# open-lab-mon-A.net
KiCad netlist of a schematic drawn in EAGLE
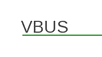
[diagram p0: schematic, sheet 1, part 1 of 2]
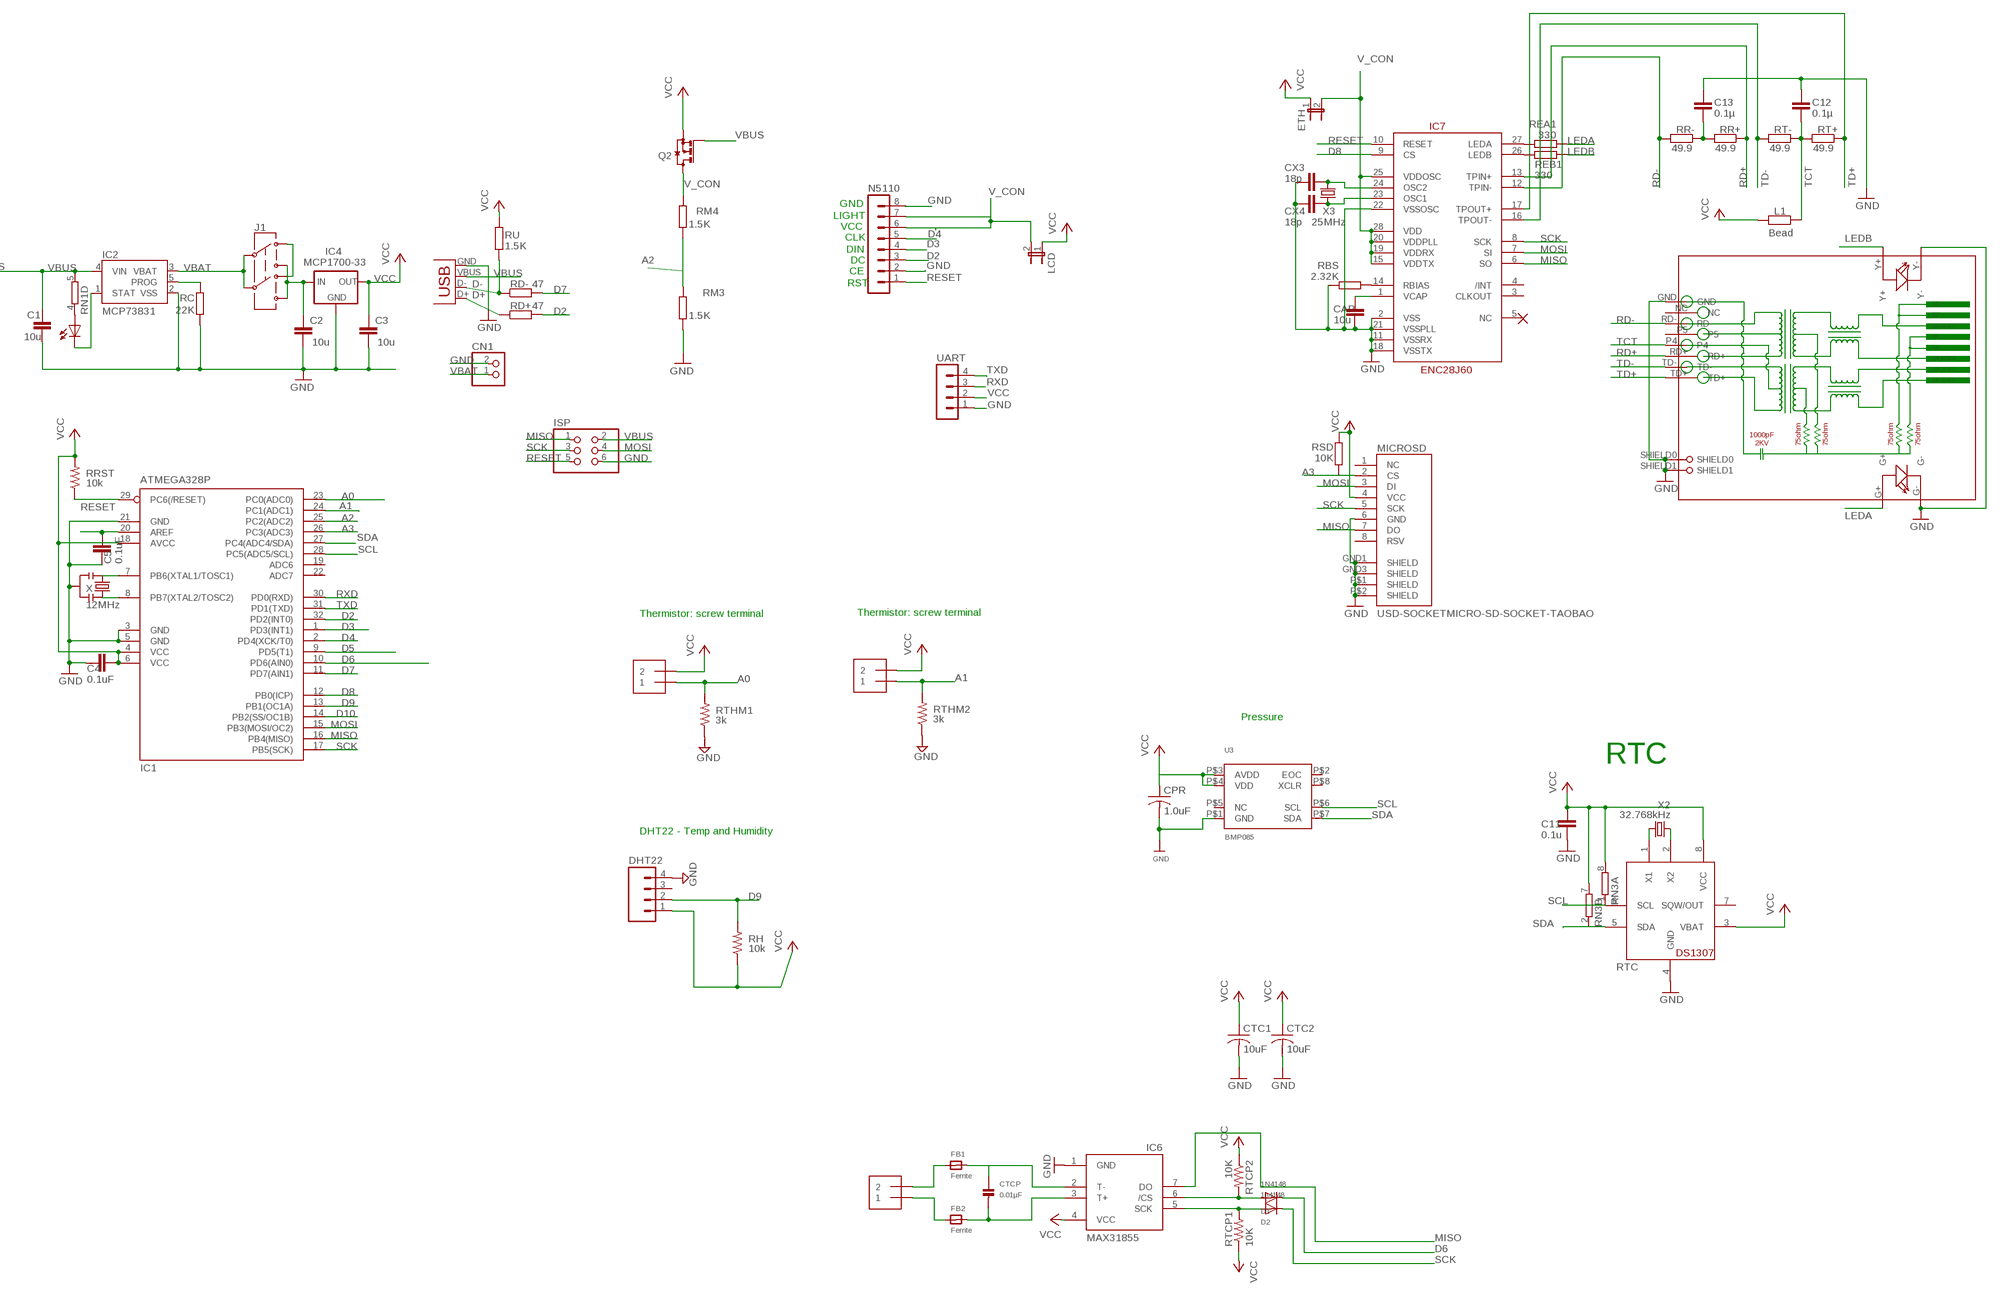
[diagram p1: schematic, sheet 1, part 2 of 2]

(export (version "E")
  (design (tool "Eeschema 10.0.6"))
  (components
    (comp (ref "C1")
      (value "10u")
      (footprint "eagle-import:C0805")
      (libsource (lib "eagle-import") (part "resistor_C-EUC0805"))
    )
    (comp (ref "C2")
      (value "10u")
      (footprint "eagle-import:C0805")
      (libsource (lib "eagle-import") (part "resistor_C-EUC0805"))
    )
    (comp (ref "C3")
      (value "10u")
      (footprint "eagle-import:C0805")
      (libsource (lib "eagle-import") (part "resistor_C-EUC0805"))
    )
    (comp (ref "C4")
      (value "0.1uF")
      (footprint "eagle-import:C0805")
      (libsource (lib "eagle-import") (part "C-EUC0805"))
    )
    (comp (ref "C5")
      (value "0.1uF")
      (footprint "eagle-import:C0805")
      (libsource (lib "eagle-import") (part "C-EUC0805"))
    )
    (comp (ref "C11")
      (value "0.1u")
      (footprint "eagle-import:C0805")
      (libsource (lib "eagle-import") (part "C-EUC0805"))
    )
    (comp (ref "C12")
      (value "0.1µ")
      (footprint "eagle-import:C0805")
      (libsource (lib "eagle-import") (part "resistor_C-EUC0805"))
    )
    (comp (ref "C13")
      (value "0.1µ")
      (footprint "eagle-import:C0805")
      (libsource (lib "eagle-import") (part "resistor_C-EUC0805"))
    )
    (comp (ref "CAP")
      (value "10u")
      (footprint "eagle-import:C0805")
      (libsource (lib "eagle-import") (part "resistor_C-EUC0805"))
    )
    (comp (ref "CHG")
      (value "0805")
      (footprint "eagle-import:CHIPLED_0805")
      (libsource (lib "eagle-import") (part "LEDCHIPLED_0805"))
    )
    (comp (ref "CN1")
      (value "JST_2PIN-SMT-RA")
      (footprint "eagle-import:JST-PH-2-SMT-RA")
      (libsource (lib "eagle-import") (part "JST_2PIN-SMT-RA"))
    )
    (comp (ref "CPR")
      (value "1.0uF")
      (footprint "eagle-import:C0805")
      (libsource (lib "eagle-import") (part "C-USC0805"))
    )
    (comp (ref "CTC1")
      (value "10uF")
      (footprint "eagle-import:C0805K")
      (libsource (lib "eagle-import") (part "C-USC0805K"))
    )
    (comp (ref "CTC2")
      (value "10uF")
      (footprint "eagle-import:C0805K")
      (libsource (lib "eagle-import") (part "C-USC0805K"))
    )
    (comp (ref "CTCP")
      (value "0.01µF")
      (footprint "eagle-import:_0805")
      (libsource (lib "eagle-import") (part "CAP_CERAMIC_0805"))
    )
    (comp (ref "CX3")
      (value "18p")
      (footprint "eagle-import:C0805")
      (libsource (lib "eagle-import") (part "resistor_C-EUC0805"))
    )
    (comp (ref "CX4")
      (value "18p")
      (footprint "eagle-import:C0805")
      (libsource (lib "eagle-import") (part "resistor_C-EUC0805"))
    )
    (comp (ref "D1")
      (value "1N4148")
      (footprint "eagle-import:SOD-323F")
      (libsource (lib "eagle-import") (part "DIODESOD-323F"))
    )
    (comp (ref "D2")
      (value "1n4148")
      (footprint "eagle-import:SOD-323F")
      (libsource (lib "eagle-import") (part "DIODESOD-323F"))
    )
    (comp (ref "DHT22")
      (value "M04LOCK")
      (footprint "eagle-import:1X04_LOCK")
      (libsource (lib "eagle-import") (part "M04LOCK"))
    )
    (comp (ref "ETH")
      (value "JP1E")
      (footprint "eagle-import:JP1")
      (libsource (lib "eagle-import") (part "JP1E"))
    )
    (comp (ref "FB1")
      (value "Ferrite")
      (footprint "eagle-import:_0805")
      (libsource (lib "eagle-import") (part "FERRITE_0805"))
    )
    (comp (ref "FB2")
      (value "Ferrite")
      (footprint "eagle-import:_0805")
      (libsource (lib "eagle-import") (part "FERRITE_0805"))
    )
    (comp (ref "IC1")
      (value "ATMEGA328P")
      (footprint "eagle-import:TQFP32-08")
      (fields (field (name "MPN") "ATMEGA8-16AU"))
      (libsource (lib "eagle-import") (part "MEGA8-AI"))
    )
    (comp (ref "IC2")
      (value "MCP73831")
      (footprint "eagle-import:SOT23-5")
      (libsource (lib "eagle-import") (part "MCP73831"))
    )
    (comp (ref "IC4")
      (value "MCP1700-33")
      (footprint "eagle-import:SOT23")
      (libsource (lib "eagle-import") (part "MCP1700SOT233"))
    )
    (comp (ref "IC6")
      (value "MAX31855")
      (footprint "eagle-import:SO08")
      (libsource (lib "eagle-import") (part "MAX6675"))
    )
    (comp (ref "IC7")
      (value "ENC28J60")
      (footprint "eagle-import:SOIC28WLONG")
      (libsource (lib "eagle-import") (part "ENC28J60SO28LONG"))
    )
    (comp (ref "ISP")
      (value "PINHD-2X3")
      (footprint "eagle-import:2X03")
      (libsource (lib "eagle-import") (part "PINHD-2X3"))
    )
    (comp (ref "J1")
      (value "AYZ0202")
      (footprint "eagle-import:AYZ0202")
      (libsource (lib "eagle-import") (part "AYZ0202"))
    )
    (comp (ref "L1")
      (value "Bead")
      (footprint "eagle-import:R0805")
      (libsource (lib "eagle-import") (part "R-EU_R0805"))
    )
    (comp (ref "LCD")
      (value "JP1E")
      (footprint "eagle-import:JP1")
      (libsource (lib "eagle-import") (part "JP1E"))
    )
    (comp (ref "MICROSD")
      (value "USD-SOCKETMICRO-SD-SOCKET-TAOBAO")
      (footprint "eagle-import:MICRO-SD-SOCKET-TAOBAO")
      (libsource (lib "eagle-import") (part "USD-SOCKETMICRO-SD-SOCKET-TAOBAO"))
    )
    (comp (ref "N5110")
      (value "MA08-1")
      (footprint "eagle-import:MA08-1")
      (libsource (lib "eagle-import") (part "MA08-1"))
    )
    (comp (ref "Q2")
      (value "BSS123")
      (footprint "eagle-import:SOT23")
      (libsource (lib "eagle-import") (part "BSS123"))
    )
    (comp (ref "RBS")
      (value "2.32K")
      (footprint "eagle-import:R0805")
      (libsource (lib "eagle-import") (part "R-EU_R0805"))
    )
    (comp (ref "RC")
      (value "22K")
      (footprint "eagle-import:R0805")
      (libsource (lib "eagle-import") (part "R-EU_R0805"))
    )
    (comp (ref "RD+")
      (value "47")
      (footprint "eagle-import:R0805")
      (libsource (lib "eagle-import") (part "R-EU_R0805"))
    )
    (comp (ref "RD-")
      (value "47")
      (footprint "eagle-import:R0805")
      (libsource (lib "eagle-import") (part "R-EU_R0805"))
    )
    (comp (ref "REA1")
      (value "330")
      (footprint "eagle-import:R0805")
      (libsource (lib "eagle-import") (part "R-EU_R0805"))
    )
    (comp (ref "REB1")
      (value "330")
      (footprint "eagle-import:R0805")
      (libsource (lib "eagle-import") (part "R-EU_R0805"))
    )
    (comp (ref "RH")
      (value "10k")
      (footprint "eagle-import:R0805@1")
      (libsource (lib "eagle-import") (part "rcl_R-US_R0805"))
    )
    (comp (ref "RJ45")
      (value "HR911105A")
      (footprint "eagle-import:HR911105A")
      (libsource (lib "eagle-import") (part "HR911105A"))
    )
    (comp (ref "RM3")
      (value "1.5K")
      (footprint "eagle-import:R0805")
      (libsource (lib "eagle-import") (part "R-EU_R0805"))
    )
    (comp (ref "RM4")
      (value "1.5K")
      (footprint "eagle-import:R0805")
      (libsource (lib "eagle-import") (part "R-EU_R0805"))
    )
    (comp (ref "RN1")
      (value "4R-NEXB38V")
      (footprint "eagle-import:EXB38V")
      (libsource (lib "eagle-import") (part "4R-NEXB38V"))
    )
    (comp (ref "RN3")
      (value "4R-NEXB38V")
      (footprint "eagle-import:EXB38V")
      (libsource (lib "eagle-import") (part "4R-NEXB38V"))
    )
    (comp (ref "RR+")
      (value "49.9")
      (footprint "eagle-import:R0805")
      (libsource (lib "eagle-import") (part "R-EU_R0805"))
    )
    (comp (ref "RR-")
      (value "49.9")
      (footprint "eagle-import:R0805")
      (libsource (lib "eagle-import") (part "R-EU_R0805"))
    )
    (comp (ref "RRST")
      (value "10k")
      (footprint "eagle-import:R0805@1")
      (libsource (lib "eagle-import") (part "rcl_R-US_R0805"))
    )
    (comp (ref "RSD")
      (value "10K")
      (footprint "eagle-import:R0805")
      (libsource (lib "eagle-import") (part "R-EU_R0805"))
    )
    (comp (ref "RT+")
      (value "49.9")
      (footprint "eagle-import:R0805")
      (libsource (lib "eagle-import") (part "R-EU_R0805"))
    )
    (comp (ref "RT-")
      (value "49.9")
      (footprint "eagle-import:R0805")
      (libsource (lib "eagle-import") (part "R-EU_R0805"))
    )
    (comp (ref "RTC")
      (value "DS1307")
      (footprint "eagle-import:SO08")
      (libsource (lib "eagle-import") (part "DS1307SOIC"))
    )
    (comp (ref "RTCP1")
      (value "10K")
      (footprint "eagle-import:R0805")
      (libsource (lib "eagle-import") (part "R-US_R0805"))
    )
    (comp (ref "RTCP2")
      (value "10K")
      (footprint "eagle-import:R0805")
      (libsource (lib "eagle-import") (part "R-US_R0805"))
    )
    (comp (ref "RTHM1")
      (value "3k")
      (footprint "eagle-import:R0805@1")
      (libsource (lib "eagle-import") (part "rcl_R-US_R0805"))
    )
    (comp (ref "RTHM2")
      (value "3k")
      (footprint "eagle-import:R0805@1")
      (libsource (lib "eagle-import") (part "rcl_R-US_R0805"))
    )
    (comp (ref "RU")
      (value "1.5K")
      (footprint "eagle-import:R0805")
      (libsource (lib "eagle-import") (part "R-EU_R0805"))
    )
    (comp (ref "TCPL")
      (value "1X2-3.5MM")
      (footprint "eagle-import:1X2-3.5MM")
      (libsource (lib "eagle-import") (part "1X2-3.5MM"))
    )
    (comp (ref "THM1")
      (value "1X2-3.5MM")
      (footprint "eagle-import:1X2-3.5MM")
      (libsource (lib "eagle-import") (part "1X2-3.5MM"))
    )
    (comp (ref "THM2")
      (value "1X2-3.5MM")
      (footprint "eagle-import:1X2-3.5MM")
      (libsource (lib "eagle-import") (part "1X2-3.5MM"))
    )
    (comp (ref "U3")
      (value "BMP085")
      (footprint "eagle-import:BMP085")
      (libsource (lib "eagle-import") (part "BMP085"))
    )
    (comp (ref "UART")
      (value "MA04-1")
      (footprint "eagle-import:MA04-1")
      (libsource (lib "eagle-import") (part "MA04-1"))
    )
    (comp (ref "X")
      (value "12MHz")
      (footprint "eagle-import:RESONATOR-SMD")
      (libsource (lib "eagle-import") (part "RESONATORSMD"))
    )
    (comp (ref "X1")
      (value "USBSMD")
      (footprint "eagle-import:USB-MINIB")
      (libsource (lib "eagle-import") (part "USBSMD"))
    )
    (comp (ref "X2")
      (value "32.768kHz")
      (footprint "eagle-import:TC26H")
      (libsource (lib "eagle-import") (part "crystal_CRYSTALTC26H"))
    )
    (comp (ref "X3")
      (value "25MHz")
      (footprint "eagle-import:HC49U-V")
      (libsource (lib "eagle-import") (part "CRYSTALHC49UV"))
    )
  )
  (nets
    (net (code "1") (name "/A0") (class "Default")
      (node (ref "IC1") (pin "23") (pinfunction "PC0(ADC0)_23") (pintype "bidirectional"))
      (node (ref "RTHM1") (pin "2") (pinfunction "2_2") (pintype "passive"))
      (node (ref "THM1") (pin "1") (pinfunction "1_1") (pintype "passive"))
    )
    (net (code "2") (name "/A1") (class "Default")
      (node (ref "IC1") (pin "24") (pinfunction "PC1(ADC1)_24") (pintype "bidirectional"))
      (node (ref "RTHM2") (pin "2") (pinfunction "2_2") (pintype "passive"))
      (node (ref "THM2") (pin "1") (pinfunction "1_1") (pintype "passive"))
    )
    (net (code "3") (name "/A2") (class "Default")
      (node (ref "IC1") (pin "25") (pinfunction "PC2(ADC2)_25") (pintype "bidirectional"))
      (node (ref "RM3") (pin "2") (pinfunction "2_2") (pintype "passive"))
      (node (ref "RM4") (pin "1") (pinfunction "1_1") (pintype "passive"))
    )
    (net (code "4") (name "/A3") (class "Default")
      (node (ref "IC1") (pin "26") (pinfunction "PC3(ADC3)_26") (pintype "bidirectional"))
      (node (ref "MICROSD") (pin "2") (pinfunction "CS_2") (pintype "bidirectional"))
      (node (ref "RSD") (pin "1") (pinfunction "1_1") (pintype "passive"))
    )
    (net (code "5") (name "/D+") (class "Default")
      (node (ref "RD+") (pin "1") (pinfunction "1_1") (pintype "passive"))
      (node (ref "X1") (pin "D+") (pinfunction "D+_D+") (pintype "bidirectional"))
    )
    (net (code "6") (name "/D-") (class "Default")
      (node (ref "RD-") (pin "1") (pinfunction "1_1") (pintype "passive"))
      (node (ref "RU") (pin "1") (pinfunction "1_1") (pintype "passive"))
      (node (ref "X1") (pin "D-") (pinfunction "D-_D-") (pintype "bidirectional"))
    )
    (net (code "7") (name "/D2") (class "Default")
      (node (ref "IC1") (pin "32") (pinfunction "PD2(INT0)_32") (pintype "bidirectional"))
      (node (ref "N5110") (pin "3") (pinfunction "3_3") (pintype "passive"))
      (node (ref "RD+") (pin "2") (pinfunction "2_2") (pintype "passive"))
    )
    (net (code "8") (name "/D3") (class "Default")
      (node (ref "IC1") (pin "1") (pinfunction "PD3(INT1)_1") (pintype "bidirectional"))
      (node (ref "N5110") (pin "4") (pinfunction "4_4") (pintype "passive"))
    )
    (net (code "9") (name "/D4") (class "Default")
      (node (ref "IC1") (pin "2") (pinfunction "PD4(XCK/T0)_2") (pintype "bidirectional"))
      (node (ref "N5110") (pin "5") (pinfunction "5_5") (pintype "passive"))
    )
    (net (code "10") (name "/D5") (class "Default")
      (node (ref "IC1") (pin "9") (pinfunction "PD5(T1)_9") (pintype "bidirectional"))
    )
    (net (code "11") (name "/D6") (class "Default")
      (node (ref "D1") (pin "C") (pinfunction "C_C") (pintype "passive"))
      (node (ref "IC1") (pin "10") (pinfunction "PD6(AIN0)_10") (pintype "bidirectional"))
    )
    (net (code "12") (name "/D7") (class "Default")
      (node (ref "IC1") (pin "11") (pinfunction "PD7(AIN1)_11") (pintype "bidirectional"))
      (node (ref "RD-") (pin "2") (pinfunction "2_2") (pintype "passive"))
    )
    (net (code "13") (name "/D8") (class "Default")
      (node (ref "IC1") (pin "12") (pinfunction "PB0(ICP)_12") (pintype "bidirectional"))
      (node (ref "IC7") (pin "9") (pinfunction "CS_9") (pintype "bidirectional"))
    )
    (net (code "14") (name "/D9") (class "Default")
      (node (ref "DHT22") (pin "2") (pinfunction "2_2") (pintype "passive"))
      (node (ref "IC1") (pin "13") (pinfunction "PB1(OC1A)_13") (pintype "bidirectional"))
      (node (ref "RH") (pin "2") (pinfunction "2_2") (pintype "passive"))
    )
    (net (code "15") (name "/D10") (class "Default")
      (node (ref "IC1") (pin "14") (pinfunction "PB2(SS/OC1B)_14") (pintype "bidirectional"))
    )
    (net (code "16") (name "/LEDA") (class "Default")
      (node (ref "REA1") (pin "2") (pinfunction "2_2") (pintype "passive"))
      (node (ref "RJ45") (pin "G+") (pinfunction "G+_G+") (pintype "bidirectional"))
    )
    (net (code "17") (name "/LEDB") (class "Default")
      (node (ref "REB1") (pin "2") (pinfunction "2_2") (pintype "passive"))
      (node (ref "RJ45") (pin "Y+") (pinfunction "Y+_Y+") (pintype "bidirectional"))
    )
    (net (code "18") (name "/MISO") (class "Default")
      (node (ref "IC1") (pin "16") (pinfunction "PB4(MISO)_16") (pintype "bidirectional"))
      (node (ref "IC6") (pin "7") (pinfunction "DO_7") (pintype "output"))
      (node (ref "IC7") (pin "6") (pinfunction "SO_6") (pintype "bidirectional"))
      (node (ref "ISP") (pin "1") (pinfunction "1_1") (pintype "passive"))
      (node (ref "MICROSD") (pin "7") (pinfunction "DO_7") (pintype "bidirectional"))
    )
    (net (code "19") (name "/MOSI") (class "Default")
      (node (ref "IC1") (pin "15") (pinfunction "PB3(MOSI/OC2)_15") (pintype "bidirectional"))
      (node (ref "IC7") (pin "7") (pinfunction "SI_7") (pintype "bidirectional"))
      (node (ref "ISP") (pin "4") (pinfunction "4_4") (pintype "passive"))
      (node (ref "MICROSD") (pin "3") (pinfunction "DI_3") (pintype "bidirectional"))
    )
    (net (code "20") (name "/RD+") (class "Default")
      (node (ref "IC7") (pin "13") (pinfunction "TPIN+_13") (pintype "bidirectional"))
      (node (ref "RJ45") (pin "RD+") (pinfunction "RD+_RD+") (pintype "bidirectional"))
      (node (ref "RR+") (pin "1") (pinfunction "1_1") (pintype "passive"))
    )
    (net (code "21") (name "/RD-") (class "Default")
      (node (ref "IC7") (pin "12") (pinfunction "TPIN-_12") (pintype "bidirectional"))
      (node (ref "RJ45") (pin "RD-") (pinfunction "RD-_RD-") (pintype "bidirectional"))
      (node (ref "RR-") (pin "2") (pinfunction "2_2") (pintype "passive"))
    )
    (net (code "22") (name "/RESET") (class "Default")
      (node (ref "IC1") (pin "29") (pinfunction "PC6(/RESET)_29") (pintype "bidirectional"))
      (node (ref "IC7") (pin "10") (pinfunction "RESET_10") (pintype "bidirectional"))
      (node (ref "ISP") (pin "5") (pinfunction "5_5") (pintype "passive"))
      (node (ref "N5110") (pin "1") (pinfunction "1_1") (pintype "passive"))
      (node (ref "RRST") (pin "1") (pinfunction "1_1") (pintype "passive"))
    )
    (net (code "23") (name "/RXD") (class "Default")
      (node (ref "IC1") (pin "30") (pinfunction "PD0(RXD)_30") (pintype "bidirectional"))
      (node (ref "UART") (pin "3") (pinfunction "3_3") (pintype "passive"))
    )
    (net (code "24") (name "/SCK") (class "Default")
      (node (ref "D2") (pin "C") (pinfunction "C_C") (pintype "passive"))
      (node (ref "IC1") (pin "17") (pinfunction "PB5(SCK)_17") (pintype "bidirectional"))
      (node (ref "IC7") (pin "8") (pinfunction "SCK_8") (pintype "bidirectional"))
      (node (ref "ISP") (pin "3") (pinfunction "3_3") (pintype "passive"))
      (node (ref "MICROSD") (pin "5") (pinfunction "SCK_5") (pintype "bidirectional"))
    )
    (net (code "25") (name "/SCL") (class "Default")
      (node (ref "IC1") (pin "28") (pinfunction "PC5(ADC5/SCL)_28") (pintype "bidirectional"))
      (node (ref "RN3") (pin "1") (pinfunction "1_1") (pintype "passive"))
      (node (ref "RTC") (pin "6") (pinfunction "SCL_6") (pintype "bidirectional"))
      (node (ref "U3") (pin "P$6") (pinfunction "SCL_P$6") (pintype "bidirectional"))
    )
    (net (code "26") (name "/SDA") (class "Default")
      (node (ref "IC1") (pin "27") (pinfunction "PC4(ADC4/SDA)_27") (pintype "bidirectional"))
      (node (ref "RN3") (pin "2") (pinfunction "1_2") (pintype "passive"))
      (node (ref "RTC") (pin "5") (pinfunction "SDA_5") (pintype "bidirectional"))
      (node (ref "U3") (pin "P$7") (pinfunction "SDA_P$7") (pintype "bidirectional"))
    )
    (net (code "27") (name "/TCT") (class "Default")
      (node (ref "C12") (pin "2") (pinfunction "2_2") (pintype "passive"))
      (node (ref "L1") (pin "1") (pinfunction "1_1") (pintype "passive"))
      (node (ref "RJ45") (pin "P4") (pinfunction "P4_P4") (pintype "bidirectional"))
      (node (ref "RT+") (pin "2") (pinfunction "2_2") (pintype "passive"))
      (node (ref "RT-") (pin "1") (pinfunction "1_1") (pintype "passive"))
    )
    (net (code "28") (name "/TD+") (class "Default")
      (node (ref "IC7") (pin "17") (pinfunction "TPOUT+_17") (pintype "bidirectional"))
      (node (ref "RJ45") (pin "TD+") (pinfunction "TD+_TD+") (pintype "bidirectional"))
      (node (ref "RT+") (pin "1") (pinfunction "1_1") (pintype "passive"))
    )
    (net (code "29") (name "/TD-") (class "Default")
      (node (ref "IC7") (pin "16") (pinfunction "TPOUT-_16") (pintype "bidirectional"))
      (node (ref "RJ45") (pin "TD-") (pinfunction "TD-_TD-") (pintype "bidirectional"))
      (node (ref "RT-") (pin "2") (pinfunction "2_2") (pintype "passive"))
    )
    (net (code "30") (name "/TXD") (class "Default")
      (node (ref "IC1") (pin "31") (pinfunction "PD1(TXD)_31") (pintype "bidirectional"))
      (node (ref "UART") (pin "4") (pinfunction "4_4") (pintype "passive"))
    )
    (net (code "31") (name "/VBAT") (class "Default")
      (node (ref "CN1") (pin "1") (pinfunction "2_1") (pintype "passive"))
      (node (ref "IC2") (pin "3") (pinfunction "VBAT_3") (pintype "power_in"))
      (node (ref "J1") (pin "2") (pinfunction "2_2") (pintype "bidirectional"))
      (node (ref "J1") (pin "5") (pinfunction "5_5") (pintype "bidirectional"))
    )
    (net (code "32") (name "/VBUS") (class "Default")
      (node (ref "C1") (pin "1") (pinfunction "1_1") (pintype "passive"))
      (node (ref "IC2") (pin "4") (pinfunction "VIN_4") (pintype "power_in"))
      (node (ref "ISP") (pin "2") (pinfunction "2_2") (pintype "passive"))
      (node (ref "Q2") (pin "1") (pinfunction "G_1") (pintype "passive"))
      (node (ref "RN1") (pin "5") (pinfunction "2_5") (pintype "passive"))
      (node (ref "X1") (pin "VBUS") (pinfunction "VBUS_VBUS") (pintype "bidirectional"))
    )
    (net (code "33") (name "/V_CON") (class "Default")
      (node (ref "ETH") (pin "2") (pinfunction "2_2") (pintype "passive"))
      (node (ref "IC7") (pin "15") (pinfunction "VDDTX_15") (pintype "bidirectional"))
      (node (ref "IC7") (pin "19") (pinfunction "VDDRX_19") (pintype "bidirectional"))
      (node (ref "IC7") (pin "20") (pinfunction "VDDPLL_20") (pintype "bidirectional"))
      (node (ref "IC7") (pin "25") (pinfunction "VDDOSC_25") (pintype "bidirectional"))
      (node (ref "IC7") (pin "28") (pinfunction "VDD_28") (pintype "bidirectional"))
      (node (ref "LCD") (pin "2") (pinfunction "2_2") (pintype "passive"))
      (node (ref "N5110") (pin "6") (pinfunction "6_6") (pintype "passive"))
      (node (ref "N5110") (pin "7") (pinfunction "7_7") (pintype "passive"))
      (node (ref "Q2") (pin "3") (pinfunction "D_3") (pintype "passive"))
      (node (ref "RM4") (pin "2") (pinfunction "2_2") (pintype "passive"))
    )
    (net (code "34") (name "GND") (class "Default")
      (node (ref "C1") (pin "2") (pinfunction "2_2") (pintype "passive"))
      (node (ref "C11") (pin "2") (pinfunction "2_2") (pintype "passive"))
      (node (ref "C12") (pin "1") (pinfunction "1_1") (pintype "passive"))
      (node (ref "C13") (pin "1") (pinfunction "1_1") (pintype "passive"))
      (node (ref "C2") (pin "2") (pinfunction "2_2") (pintype "passive"))
      (node (ref "C3") (pin "2") (pinfunction "2_2") (pintype "passive"))
      (node (ref "C4") (pin "1") (pinfunction "1_1") (pintype "passive"))
      (node (ref "C5") (pin "1") (pinfunction "1_1") (pintype "passive"))
      (node (ref "CAP") (pin "2") (pinfunction "2_2") (pintype "passive"))
      (node (ref "CN1") (pin "2") (pinfunction "1_2") (pintype "passive"))
      (node (ref "CPR") (pin "2") (pinfunction "2_2") (pintype "passive"))
      (node (ref "CTC1") (pin "2") (pinfunction "2_2") (pintype "passive"))
      (node (ref "CTC2") (pin "2") (pinfunction "2_2") (pintype "passive"))
      (node (ref "CX3") (pin "2") (pinfunction "2_2") (pintype "passive"))
      (node (ref "CX4") (pin "2") (pinfunction "2_2") (pintype "passive"))
      (node (ref "DHT22") (pin "4") (pinfunction "4_4") (pintype "passive"))
      (node (ref "IC1") (pin "21") (pinfunction "GND_21") (pintype "power_in"))
      (node (ref "IC1") (pin "3") (pinfunction "GND_3") (pintype "power_in"))
      (node (ref "IC1") (pin "5") (pinfunction "GND_5") (pintype "power_in"))
      (node (ref "IC2") (pin "2") (pinfunction "VSS_2") (pintype "power_in"))
      (node (ref "IC4") (pin "1") (pinfunction "GND_1") (pintype "input"))
      (node (ref "IC6") (pin "1") (pinfunction "GND_1") (pintype "power_in"))
      (node (ref "IC7") (pin "11") (pinfunction "VSSRX_11") (pintype "bidirectional"))
      (node (ref "IC7") (pin "18") (pinfunction "VSSTX_18") (pintype "bidirectional"))
      (node (ref "IC7") (pin "2") (pinfunction "VSS_2") (pintype "bidirectional"))
      (node (ref "IC7") (pin "21") (pinfunction "VSSPLL_21") (pintype "bidirectional"))
      (node (ref "IC7") (pin "22") (pinfunction "VSSOSC_22") (pintype "bidirectional"))
      (node (ref "ISP") (pin "6") (pinfunction "6_6") (pintype "passive"))
      (node (ref "MICROSD") (pin "6") (pinfunction "GND_6") (pintype "bidirectional"))
      (node (ref "MICROSD") (pin "GND1") (pinfunction "SHIELD_GND1") (pintype "bidirectional"))
      (node (ref "MICROSD") (pin "GND3") (pinfunction "SHIELD_GND3") (pintype "bidirectional"))
      (node (ref "MICROSD") (pin "P$1") (pinfunction "SHIELD_P$1") (pintype "bidirectional"))
      (node (ref "MICROSD") (pin "P$2") (pinfunction "SHIELD_P$2") (pintype "bidirectional"))
      (node (ref "N5110") (pin "2") (pinfunction "2_2") (pintype "passive"))
      (node (ref "RBS") (pin "1") (pinfunction "1_1") (pintype "passive"))
      (node (ref "RC") (pin "1") (pinfunction "1_1") (pintype "passive"))
      (node (ref "RJ45") (pin "G-") (pinfunction "G-_G-") (pintype "bidirectional"))
      (node (ref "RJ45") (pin "GND") (pinfunction "GND_GND") (pintype "bidirectional"))
      (node (ref "RJ45") (pin "SHIELD0") (pinfunction "SHIELD0_SHIELD0") (pintype "bidirectional"))
      (node (ref "RJ45") (pin "SHIELD1") (pinfunction "SHIELD1_SHIELD1") (pintype "bidirectional"))
      (node (ref "RJ45") (pin "Y-") (pinfunction "Y-_Y-") (pintype "bidirectional"))
      (node (ref "RM3") (pin "1") (pinfunction "1_1") (pintype "passive"))
      (node (ref "RTC") (pin "4") (pinfunction "GND_4") (pintype "power_in"))
      (node (ref "RTHM1") (pin "1") (pinfunction "1_1") (pintype "passive"))
      (node (ref "RTHM2") (pin "1") (pinfunction "1_1") (pintype "passive"))
      (node (ref "U3") (pin "P$1") (pinfunction "GND_P$1") (pintype "bidirectional"))
      (node (ref "UART") (pin "1") (pinfunction "1_1") (pintype "passive"))
      (node (ref "X") (pin "2") (pinfunction "2_2") (pintype "passive"))
      (node (ref "X1") (pin "GND") (pinfunction "GND_GND") (pintype "bidirectional"))
    )
    (net (code "35") (name "Net-(C13-Pad2)") (class "Default")
      (node (ref "C13") (pin "2") (pinfunction "2_2") (pintype "passive"))
      (node (ref "RR+") (pin "2") (pinfunction "2_2") (pintype "passive"))
      (node (ref "RR-") (pin "1") (pinfunction "1_1") (pintype "passive"))
    )
    (net (code "36") (name "Net-(CTCP-P$1)") (class "Default")
      (node (ref "CTCP") (pin "1") (pinfunction "P$1_1") (pintype "passive"))
      (node (ref "FB1") (pin "2") (pinfunction "P$2_2") (pintype "passive"))
      (node (ref "IC6") (pin "2") (pinfunction "T-_2") (pintype "input"))
    )
    (net (code "37") (name "Net-(CTCP-P$2)") (class "Default")
      (node (ref "CTCP") (pin "2") (pinfunction "P$2_2") (pintype "passive"))
      (node (ref "FB2") (pin "2") (pinfunction "P$2_2") (pintype "passive"))
      (node (ref "IC6") (pin "3") (pinfunction "T+_3") (pintype "input"))
    )
    (net (code "38") (name "Net-(FB1-P$1)") (class "Default")
      (node (ref "FB1") (pin "1") (pinfunction "P$1_1") (pintype "passive"))
      (node (ref "TCPL") (pin "2") (pinfunction "2_2") (pintype "passive"))
    )
    (net (code "39") (name "Net-(FB2-P$1)") (class "Default")
      (node (ref "FB2") (pin "1") (pinfunction "P$1_1") (pintype "passive"))
      (node (ref "TCPL") (pin "1") (pinfunction "1_1") (pintype "passive"))
    )
    (net (code "40") (name "Net-(IC1-AREF)") (class "Default")
      (node (ref "C5") (pin "2") (pinfunction "2_2") (pintype "passive"))
      (node (ref "IC1") (pin "20") (pinfunction "AREF_20") (pintype "passive"))
    )
    (net (code "41") (name "Net-(IC1-PB6(XTAL1{slash}TOSC1))") (class "Default")
      (node (ref "IC1") (pin "7") (pinfunction "PB6(XTAL1/TOSC1)_7") (pintype "bidirectional"))
      (node (ref "X") (pin "1") (pinfunction "1_1") (pintype "passive"))
    )
    (net (code "42") (name "Net-(IC1-PB7(XTAL2{slash}TOSC2))") (class "Default")
      (node (ref "IC1") (pin "8") (pinfunction "PB7(XTAL2/TOSC2)_8") (pintype "bidirectional"))
      (node (ref "X") (pin "3") (pinfunction "3_3") (pintype "passive"))
    )
    (net (code "43") (name "Net-(IC2-PROG)") (class "Default")
      (node (ref "IC2") (pin "5") (pinfunction "PROG_5") (pintype "input"))
      (node (ref "RC") (pin "2") (pinfunction "2_2") (pintype "passive"))
    )
    (net (code "44") (name "Net-(IC2-STAT)") (class "Default")
      (node (ref "CHG") (pin "C") (pinfunction "C_C") (pintype "passive"))
      (node (ref "IC2") (pin "1") (pinfunction "STAT_1") (pintype "output"))
    )
    (net (code "45") (name "Net-(IC4-IN)") (class "Default")
      (node (ref "C2") (pin "1") (pinfunction "1_1") (pintype "passive"))
      (node (ref "IC4") (pin "3") (pinfunction "IN_3") (pintype "input"))
      (node (ref "J1") (pin "1") (pinfunction "3_1") (pintype "bidirectional"))
      (node (ref "J1") (pin "4") (pinfunction "6_4") (pintype "bidirectional"))
    )
    (net (code "46") (name "Net-(IC6-SCK)") (class "Default")
      (node (ref "D2") (pin "A") (pinfunction "A_A") (pintype "passive"))
      (node (ref "IC6") (pin "5") (pinfunction "SCK_5") (pintype "input"))
      (node (ref "RTCP1") (pin "2") (pinfunction "2_2") (pintype "passive"))
    )
    (net (code "47") (name "Net-(IC6-{slash}CS)") (class "Default")
      (node (ref "D1") (pin "A") (pinfunction "A_A") (pintype "passive"))
      (node (ref "IC6") (pin "6") (pinfunction "/CS_6") (pintype "input"))
      (node (ref "RTCP2") (pin "2") (pinfunction "2_2") (pintype "passive"))
    )
    (net (code "48") (name "Net-(IC7-LEDA)") (class "Default")
      (node (ref "IC7") (pin "27") (pinfunction "LEDA_27") (pintype "bidirectional"))
      (node (ref "REA1") (pin "1") (pinfunction "1_1") (pintype "passive"))
    )
    (net (code "49") (name "Net-(IC7-LEDB)") (class "Default")
      (node (ref "IC7") (pin "26") (pinfunction "LEDB_26") (pintype "bidirectional"))
      (node (ref "REB1") (pin "1") (pinfunction "1_1") (pintype "passive"))
    )
    (net (code "50") (name "Net-(IC7-OSC1)") (class "Default")
      (node (ref "CX4") (pin "1") (pinfunction "1_1") (pintype "passive"))
      (node (ref "IC7") (pin "23") (pinfunction "OSC1_23") (pintype "bidirectional"))
      (node (ref "X3") (pin "1") (pinfunction "1_1") (pintype "passive"))
    )
    (net (code "51") (name "Net-(IC7-OSC2)") (class "Default")
      (node (ref "CX3") (pin "1") (pinfunction "1_1") (pintype "passive"))
      (node (ref "IC7") (pin "24") (pinfunction "OSC2_24") (pintype "bidirectional"))
      (node (ref "X3") (pin "2") (pinfunction "2_2") (pintype "passive"))
    )
    (net (code "52") (name "Net-(IC7-RBIAS)") (class "Default")
      (node (ref "IC7") (pin "14") (pinfunction "RBIAS_14") (pintype "bidirectional"))
      (node (ref "RBS") (pin "2") (pinfunction "2_2") (pintype "passive"))
    )
    (net (code "53") (name "Net-(IC7-VCAP)") (class "Default")
      (node (ref "CAP") (pin "1") (pinfunction "1_1") (pintype "passive"))
      (node (ref "IC7") (pin "1") (pinfunction "VCAP_1") (pintype "bidirectional"))
    )
    (net (code "54") (name "Net-(J1-1)") (class "Default")
      (node (ref "J1") (pin "3") (pinfunction "1_3") (pintype "bidirectional"))
      (node (ref "J1") (pin "6") (pinfunction "4_6") (pintype "bidirectional"))
    )
    (net (code "55") (name "Net-(RN1D-1)") (class "Default")
      (node (ref "CHG") (pin "A") (pinfunction "A_A") (pintype "passive"))
      (node (ref "RN1") (pin "4") (pinfunction "1_4") (pintype "passive"))
    )
    (net (code "56") (name "Net-(RTC-X1)") (class "Default")
      (node (ref "RTC") (pin "1") (pinfunction "X1_1") (pintype "passive"))
      (node (ref "X2") (pin "2") (pinfunction "2_2") (pintype "passive"))
    )
    (net (code "57") (name "Net-(RTC-X2)") (class "Default")
      (node (ref "RTC") (pin "2") (pinfunction "X2_2") (pintype "passive"))
      (node (ref "X2") (pin "1") (pinfunction "1_1") (pintype "passive"))
    )
    (net (code "58") (name "VCC") (class "Default")
      (node (ref "C11") (pin "1") (pinfunction "1_1") (pintype "passive"))
      (node (ref "C3") (pin "1") (pinfunction "1_1") (pintype "passive"))
      (node (ref "C4") (pin "2") (pinfunction "2_2") (pintype "passive"))
      (node (ref "CPR") (pin "1") (pinfunction "1_1") (pintype "passive"))
      (node (ref "CTC1") (pin "1") (pinfunction "1_1") (pintype "passive"))
      (node (ref "CTC2") (pin "1") (pinfunction "1_1") (pintype "passive"))
      (node (ref "DHT22") (pin "1") (pinfunction "1_1") (pintype "passive"))
      (node (ref "ETH") (pin "1") (pinfunction "1_1") (pintype "passive"))
      (node (ref "IC1") (pin "18") (pinfunction "AVCC_18") (pintype "power_in"))
      (node (ref "IC1") (pin "4") (pinfunction "VCC_4") (pintype "power_in"))
      (node (ref "IC1") (pin "6") (pinfunction "VCC_6") (pintype "power_in"))
      (node (ref "IC4") (pin "2") (pinfunction "OUT_2") (pintype "passive"))
      (node (ref "IC6") (pin "4") (pinfunction "VCC_4") (pintype "power_in"))
      (node (ref "L1") (pin "2") (pinfunction "2_2") (pintype "passive"))
      (node (ref "LCD") (pin "1") (pinfunction "1_1") (pintype "passive"))
      (node (ref "MICROSD") (pin "4") (pinfunction "VCC_4") (pintype "bidirectional"))
      (node (ref "Q2") (pin "2") (pinfunction "S_2") (pintype "passive"))
      (node (ref "RH") (pin "1") (pinfunction "1_1") (pintype "passive"))
      (node (ref "RN3") (pin "7") (pinfunction "2_7") (pintype "passive"))
      (node (ref "RN3") (pin "8") (pinfunction "2_8") (pintype "passive"))
      (node (ref "RRST") (pin "2") (pinfunction "2_2") (pintype "passive"))
      (node (ref "RSD") (pin "2") (pinfunction "2_2") (pintype "passive"))
      (node (ref "RTC") (pin "3") (pinfunction "VBAT_3") (pintype "power_in"))
      (node (ref "RTC") (pin "8") (pinfunction "VCC_8") (pintype "power_in"))
      (node (ref "RTCP1") (pin "1") (pinfunction "1_1") (pintype "passive"))
      (node (ref "RTCP2") (pin "1") (pinfunction "1_1") (pintype "passive"))
      (node (ref "RU") (pin "2") (pinfunction "2_2") (pintype "passive"))
      (node (ref "THM1") (pin "2") (pinfunction "2_2") (pintype "passive"))
      (node (ref "THM2") (pin "2") (pinfunction "2_2") (pintype "passive"))
      (node (ref "U3") (pin "P$3") (pinfunction "AVDD_P$3") (pintype "bidirectional"))
      (node (ref "U3") (pin "P$4") (pinfunction "VDD_P$4") (pintype "bidirectional"))
      (node (ref "UART") (pin "2") (pinfunction "2_2") (pintype "passive"))
    )
    (net (code "59") (name "unconnected-(DHT22-Pad3)") (class "Default")
      (node (ref "DHT22") (pin "3") (pinfunction "3_3") (pintype "passive"))
    )
    (net (code "60") (name "unconnected-(IC1-ADC6-Pad19)") (class "Default")
      (node (ref "IC1") (pin "19") (pinfunction "ADC6_19") (pintype "bidirectional"))
    )
    (net (code "61") (name "unconnected-(IC1-ADC7-Pad22)") (class "Default")
      (node (ref "IC1") (pin "22") (pinfunction "ADC7_22") (pintype "bidirectional"))
    )
    (net (code "62") (name "unconnected-(IC7-CLKOUT-Pad3)") (class "Default")
      (node (ref "IC7") (pin "3") (pinfunction "CLKOUT_3") (pintype "bidirectional"))
    )
    (net (code "63") (name "unconnected-(IC7-NC-Pad5)") (class "Default")
      (node (ref "IC7") (pin "5") (pinfunction "NC_5") (pintype "bidirectional"))
    )
    (net (code "64") (name "unconnected-(IC7-{slash}INT-Pad4)") (class "Default")
      (node (ref "IC7") (pin "4") (pinfunction "/INT_4") (pintype "bidirectional"))
    )
    (net (code "65") (name "unconnected-(MICROSD-NC-Pad1)") (class "Default")
      (node (ref "MICROSD") (pin "1") (pinfunction "NC_1") (pintype "bidirectional"))
    )
    (net (code "66") (name "unconnected-(MICROSD-RSV-Pad8)") (class "Default")
      (node (ref "MICROSD") (pin "8") (pinfunction "RSV_8") (pintype "bidirectional"))
    )
    (net (code "67") (name "unconnected-(N5110-Pad8)") (class "Default")
      (node (ref "N5110") (pin "8") (pinfunction "8_8") (pintype "passive"))
    )
    (net (code "68") (name "unconnected-(RJ45-PadNC)") (class "Default")
      (node (ref "RJ45") (pin "NC") (pinfunction "NC_NC") (pintype "bidirectional"))
    )
    (net (code "69") (name "unconnected-(RJ45-PadP5)") (class "Default")
      (node (ref "RJ45") (pin "P5") (pinfunction "P5_P5") (pintype "bidirectional"))
    )
    (net (code "70") (name "unconnected-(RTC-SQW{slash}OUT-Pad7)") (class "Default")
      (node (ref "RTC") (pin "7") (pinfunction "SQW/OUT_7") (pintype "bidirectional"))
    )
    (net (code "71") (name "unconnected-(U3-EOC-PadP$2)") (class "Default")
      (node (ref "U3") (pin "P$2") (pinfunction "EOC_P$2") (pintype "bidirectional"))
    )
    (net (code "72") (name "unconnected-(U3-NC-PadP$5)") (class "Default")
      (node (ref "U3") (pin "P$5") (pinfunction "NC_P$5") (pintype "bidirectional"))
    )
    (net (code "73") (name "unconnected-(U3-XCLR-PadP$8)") (class "Default")
      (node (ref "U3") (pin "P$8") (pinfunction "XCLR_P$8") (pintype "bidirectional"))
    )
  )
)
